# JTAG_VOLT_TRNS.net
KiCad netlist of a schematic drawn in Altium Designer
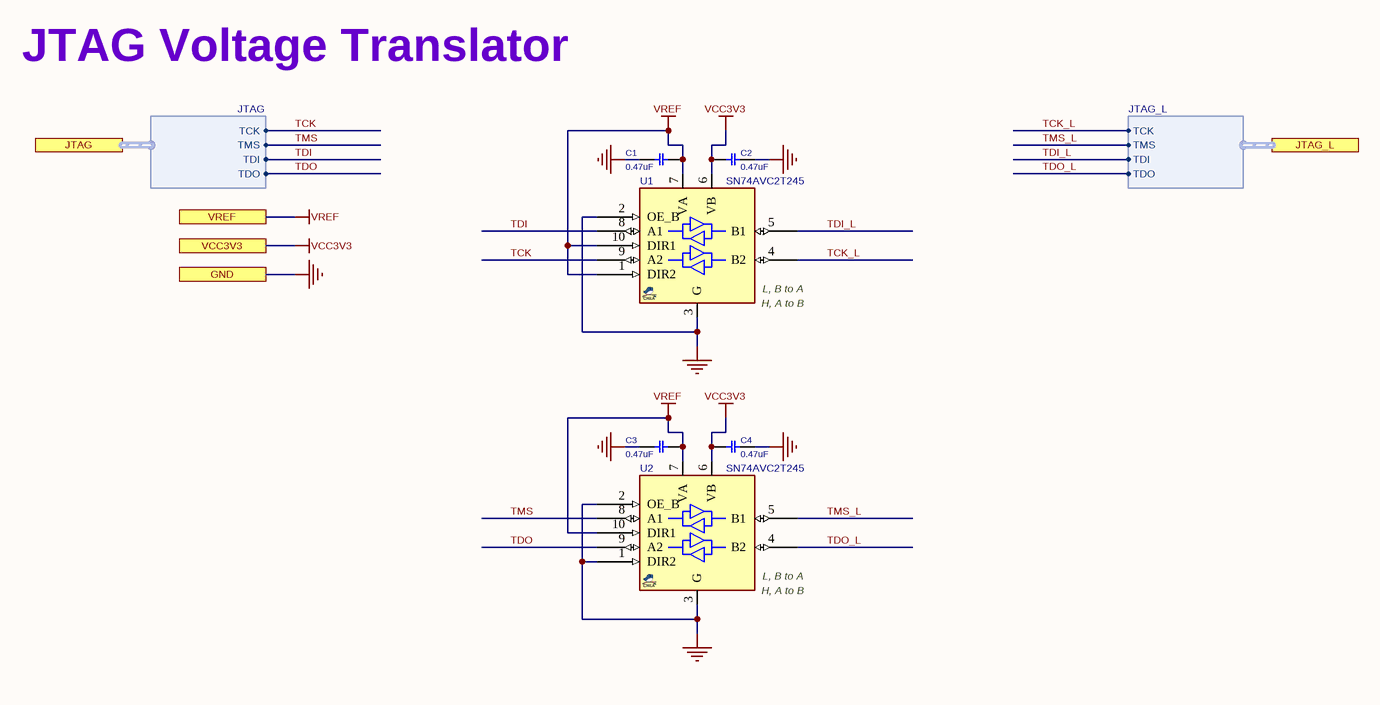
[diagram p0: JTAG_VOLT_TRNS.SchDoc]

(export (version "E")
  (design (tool "Eeschema 10.0.6"))
  (components
    (comp (ref "C1")
      (value "0.47uF")
      (footprint "C0402")
      (description "CAP, MLCC, 100nF, 50V, X7R, 10%, 0402C")
      (fields (field (name "MANF_P#") "GCM155R71H104KE02D") (field (name "MANF") "Murata"))
      (libsource (lib "mlcc_smd_passive") (part "CAP_SMD_MLCC_100n50TDK"))
    )
    (comp (ref "C2")
      (value "0.47uF")
      (footprint "C0402")
      (description "CAP, MLCC, 100nF, 50V, X7R, 10%, 0402C")
      (fields (field (name "MANF_P#") "GCM155R71H104KE02D") (field (name "MANF") "Murata"))
      (libsource (lib "mlcc_smd_passive") (part "CAP_SMD_MLCC_100n50TDK"))
    )
    (comp (ref "C3")
      (value "0.47uF")
      (footprint "C0402")
      (description "CAP, MLCC, 100nF, 50V, X7R, 10%, 0402C")
      (fields (field (name "MANF_P#") "GCM155R71H104KE02D") (field (name "MANF") "Murata"))
      (libsource (lib "mlcc_smd_passive") (part "CAP_SMD_MLCC_100n50TDK"))
    )
    (comp (ref "C4")
      (value "0.47uF")
      (footprint "C0402")
      (description "CAP, MLCC, 100nF, 50V, X7R, 10%, 0402C")
      (fields (field (name "MANF_P#") "GCM155R71H104KE02D") (field (name "MANF") "Murata"))
      (libsource (lib "mlcc_smd_passive") (part "CAP_SMD_MLCC_100n50TDK"))
    )
    (comp (ref "U1")
      (value "SN74AVC2T245")
      (footprint "QFN40_10_1418")
      (description "Level Translator, Dual, 3State")
      (fields (field (name "MANF") "TEXAS INSTRUMENTS") (field (name "MANF_P#") "SN74AVC2T245RSWR"))
      (libsource (lib "buffer_digital") (part "SN74AVC2T245_PUQFN"))
    )
    (comp (ref "U2")
      (value "SN74AVC2T245")
      (footprint "QFN40_10_1418")
      (description "Level Translator, Dual, 3State")
      (fields (field (name "MANF") "TEXAS INSTRUMENTS") (field (name "MANF_P#") "SN74AVC2T245RSWR"))
      (libsource (lib "buffer_digital") (part "SN74AVC2T245_PUQFN"))
    )
  )
  (nets
    (net (code "3") (name "/TCK") (class "Default")
      (node (ref "U1") (pin "9") (pinfunction "A2_9") (pintype "bidirectional"))
    )
    (net (code "4") (name "/TCK_L") (class "Default")
      (node (ref "U1") (pin "4") (pinfunction "B2_4") (pintype "bidirectional"))
    )
    (net (code "5") (name "/TDI") (class "Default")
      (node (ref "U1") (pin "8") (pinfunction "A1_8") (pintype "bidirectional"))
    )
    (net (code "6") (name "/TDI_L") (class "Default")
      (node (ref "U1") (pin "5") (pinfunction "B1_5") (pintype "bidirectional"))
    )
    (net (code "7") (name "/TDO") (class "Default")
      (node (ref "U2") (pin "9") (pinfunction "A2_9") (pintype "bidirectional"))
    )
    (net (code "8") (name "/TDO_L") (class "Default")
      (node (ref "U2") (pin "4") (pinfunction "B2_4") (pintype "bidirectional"))
    )
    (net (code "9") (name "/TMS") (class "Default")
      (node (ref "U2") (pin "8") (pinfunction "A1_8") (pintype "bidirectional"))
    )
    (net (code "10") (name "/TMS_L") (class "Default")
      (node (ref "U2") (pin "5") (pinfunction "B1_5") (pintype "bidirectional"))
    )
    (net (code "13") (name "GND") (class "Default")
      (node (ref "C1") (pin "2") (pinfunction "2_2") (pintype "passive"))
      (node (ref "C2") (pin "1") (pinfunction "1_1") (pintype "passive"))
      (node (ref "C3") (pin "2") (pinfunction "2_2") (pintype "passive"))
      (node (ref "C4") (pin "1") (pinfunction "1_1") (pintype "passive"))
      (node (ref "U1") (pin "2") (pinfunction "OE_B_2") (pintype "input"))
      (node (ref "U1") (pin "3") (pinfunction "G_3") (pintype "passive"))
      (node (ref "U2") (pin "1") (pinfunction "DIR2_1") (pintype "input"))
      (node (ref "U2") (pin "2") (pinfunction "OE_B_2") (pintype "input"))
      (node (ref "U2") (pin "3") (pinfunction "G_3") (pintype "passive"))
    )
    (net (code "14") (name "VCC3V3") (class "Default")
      (node (ref "C2") (pin "2") (pinfunction "2_2") (pintype "passive"))
      (node (ref "C4") (pin "2") (pinfunction "2_2") (pintype "passive"))
      (node (ref "U1") (pin "6") (pinfunction "VB_6") (pintype "passive"))
      (node (ref "U2") (pin "6") (pinfunction "VB_6") (pintype "passive"))
    )
    (net (code "15") (name "VREF") (class "Default")
      (node (ref "C1") (pin "1") (pinfunction "1_1") (pintype "passive"))
      (node (ref "C3") (pin "1") (pinfunction "1_1") (pintype "passive"))
      (node (ref "U1") (pin "1") (pinfunction "DIR2_1") (pintype "input"))
      (node (ref "U1") (pin "10") (pinfunction "DIR1_10") (pintype "input"))
      (node (ref "U1") (pin "7") (pinfunction "VA_7") (pintype "passive"))
      (node (ref "U2") (pin "10") (pinfunction "DIR1_10") (pintype "input"))
      (node (ref "U2") (pin "7") (pinfunction "VA_7") (pintype "passive"))
    )
  )
)
